# mcu.net
KiCad netlist of a schematic drawn in Altium Designer
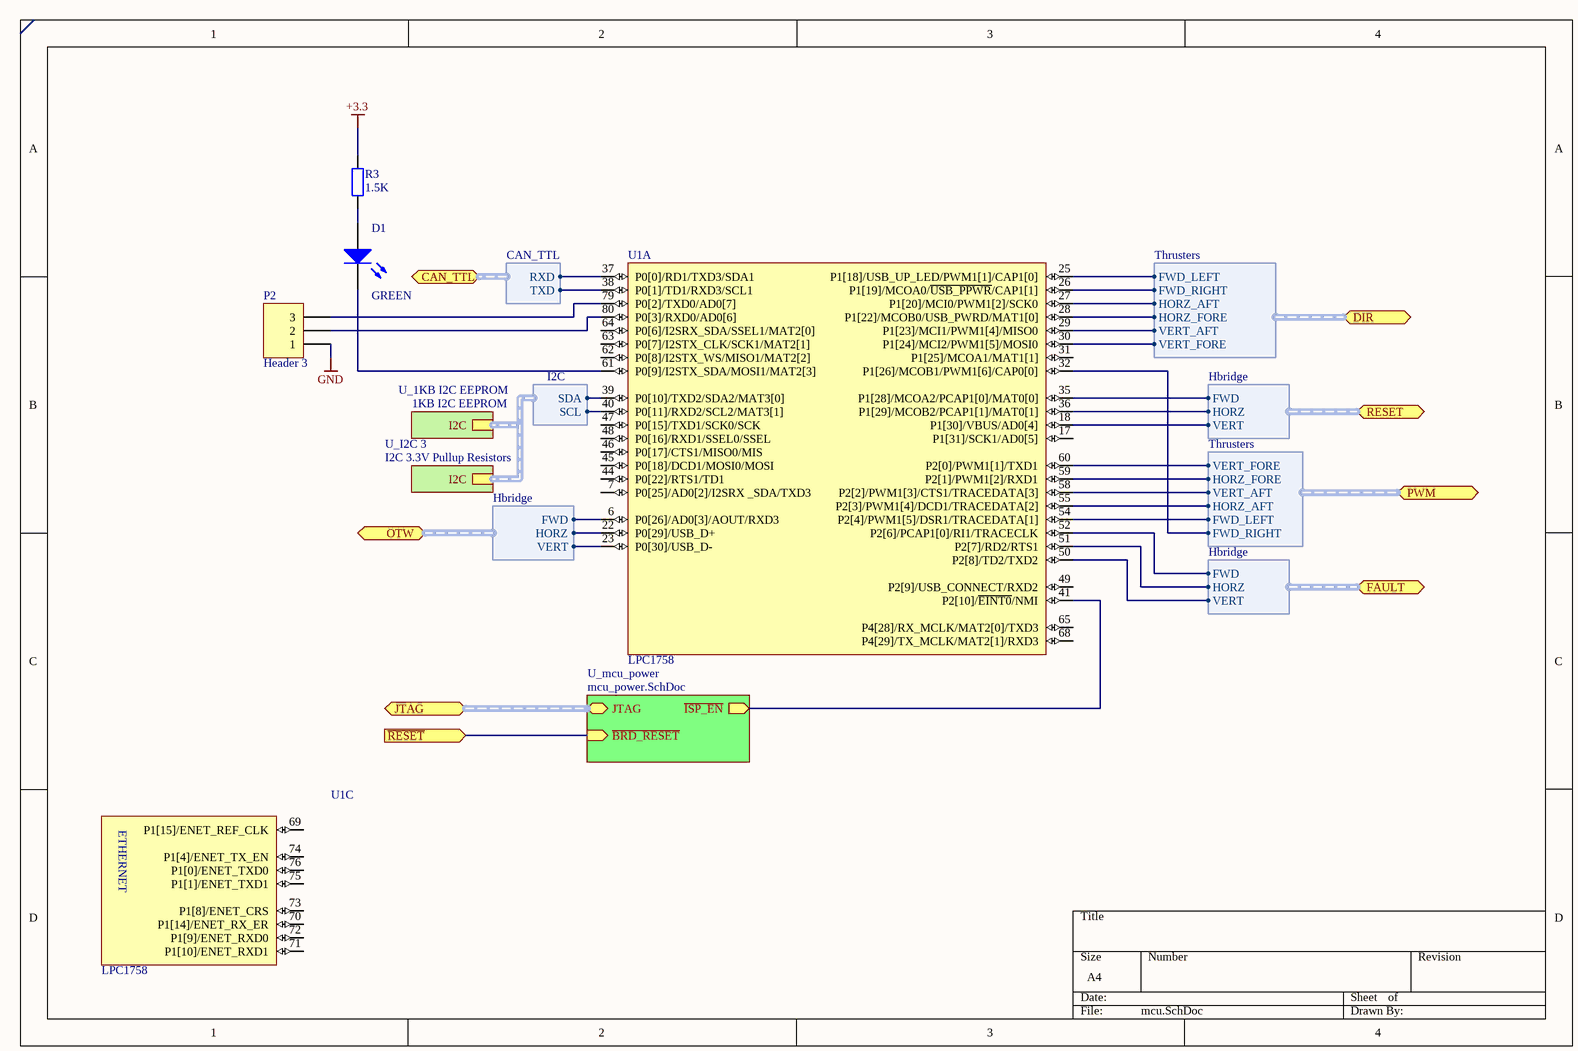
[diagram p0: mcu.SchDoc]

(export (version "E")
  (design (tool "Eeschema 10.0.6"))
  (components
    (comp (ref "D1")
      (value "GREEN")
      (footprint "LGQ971")
      (description "Typical RED, GREEN, YELLOW, AMBER GaAs LED")
      (libsource (lib "Miscellaneous Devices") (part "LED2"))
    )
    (comp (ref "P2")
      (value "Header 3")
      (footprint "HDR1X3")
      (description "Header, 3-Pin")
      (fields (field (name "PUBLISHER") "Altium Limited"))
      (libsource (lib "Miscellaneous Connectors") (part "Header 3"))
    )
    (comp (ref "R3")
      (value "1.5K")
      (footprint "R0603")
      (description "Resistor")
      (fields (field (name "Comment") "Res"))
      (libsource (lib "Miscellaneous Devices") (part "Res2"))
    )
    (comp (ref "U1")
      (value "LPC1758")
      (footprint "LPC1758FBD80")
      (description "NXP - LPC1758FBD80 - MCU, 32BIT, ARM CORTEX M3, 80LQFP")
      (libsource (lib "LPC1758") (part "LPC1758"))
    )
  )
  (nets
    (net (code "6") (name "+3.3") (class "Default")
      (node (ref "R3") (pin "2") (pinfunction "2_2") (pintype "passive"))
    )
    (net (code "8") (name "/RXD") (class "Default")
      (node (ref "U1") (pin "37") (pinfunction "P0[0]/RD1/TXD3/SDA1_37") (pintype "bidirectional"))
    )
    (net (code "9") (name "/SCL") (class "Default")
      (node (ref "U1") (pin "40") (pinfunction "P0[11]/RXD2/SCL2/MAT3[1]_40") (pintype "bidirectional"))
    )
    (net (code "10") (name "/SDA") (class "Default")
      (node (ref "U1") (pin "39") (pinfunction "P0[10]/TXD2/SDA2/MAT3[0]_39") (pintype "bidirectional"))
    )
    (net (code "11") (name "/TXD") (class "Default")
      (node (ref "U1") (pin "38") (pinfunction "P0[1]/TD1/RXD3/SCL1_38") (pintype "bidirectional"))
    )
    (net (code "16") (name "/~{ISP_EN}") (class "Default")
      (node (ref "U1") (pin "41") (pinfunction "P2[10]/~{EINT0}/NMI_41") (pintype "bidirectional"))
    )
    (net (code "18") (name "GND") (class "Default")
      (node (ref "P2") (pin "1") (pinfunction "1_1") (pintype "passive"))
    )
    (net (code "19") (name "Net-(D1-A)") (class "Default")
      (node (ref "D1") (pin "1") (pinfunction "A_1") (pintype "passive"))
      (node (ref "R3") (pin "1") (pinfunction "1_1") (pintype "passive"))
    )
    (net (code "20") (name "Net-(D1-K)") (class "Default")
      (node (ref "D1") (pin "2") (pinfunction "K_2") (pintype "passive"))
      (node (ref "U1") (pin "61") (pinfunction "P0[9]/I2STX_SDA/MOSI1/MAT2[3]_61") (pintype "bidirectional"))
    )
    (net (code "21") (name "Net-(U1A-P0[2]{slash}TXD0{slash}AD0[7])") (class "Default")
      (node (ref "P2") (pin "3") (pinfunction "3_3") (pintype "passive"))
      (node (ref "U1") (pin "79") (pinfunction "P0[2]/TXD0/AD0[7]_79") (pintype "bidirectional"))
    )
    (net (code "22") (name "Net-(U1A-P0[3]{slash}RXD0{slash}AD0[6])") (class "Default")
      (node (ref "P2") (pin "2") (pinfunction "2_2") (pintype "passive"))
      (node (ref "U1") (pin "80") (pinfunction "P0[3]/RXD0/AD0[6]_80") (pintype "bidirectional"))
    )
    (net (code "23") (name "unconnected-(U1A-P0[6]{slash}I2SRX_SDA{slash}SSEL1{slash}MAT2[0]-Pad64)") (class "Default")
      (node (ref "U1") (pin "64") (pinfunction "P0[6]/I2SRX_SDA/SSEL1/MAT2[0]_64") (pintype "bidirectional"))
    )
    (net (code "24") (name "unconnected-(U1A-P0[7]{slash}I2STX_CLK{slash}SCK1{slash}MAT2[1]-Pad63)") (class "Default")
      (node (ref "U1") (pin "63") (pinfunction "P0[7]/I2STX_CLK/SCK1/MAT2[1]_63") (pintype "bidirectional"))
    )
    (net (code "25") (name "unconnected-(U1A-P0[8]{slash}I2STX_WS{slash}MISO1{slash}MAT2[2]-Pad62)") (class "Default")
      (node (ref "U1") (pin "62") (pinfunction "P0[8]/I2STX_WS/MISO1/MAT2[2]_62") (pintype "bidirectional"))
    )
    (net (code "26") (name "unconnected-(U1A-P0[15]{slash}TXD1{slash}SCK0{slash}SCK-Pad47)") (class "Default")
      (node (ref "U1") (pin "47") (pinfunction "P0[15]/TXD1/SCK0/SCK_47") (pintype "bidirectional"))
    )
    (net (code "27") (name "unconnected-(U1A-P0[16]{slash}RXD1{slash}SSEL0{slash}SSEL-Pad48)") (class "Default")
      (node (ref "U1") (pin "48") (pinfunction "P0[16]/RXD1/SSEL0/SSEL_48") (pintype "bidirectional"))
    )
    (net (code "28") (name "unconnected-(U1A-P0[17]{slash}CTS1{slash}MISO0{slash}MIS-Pad46)") (class "Default")
      (node (ref "U1") (pin "46") (pinfunction "P0[17]/CTS1/MISO0/MIS_46") (pintype "bidirectional"))
    )
    (net (code "29") (name "unconnected-(U1A-P0[18]{slash}DCD1{slash}MOSI0{slash}MOSI-Pad45)") (class "Default")
      (node (ref "U1") (pin "45") (pinfunction "P0[18]/DCD1/MOSI0/MOSI_45") (pintype "bidirectional"))
    )
    (net (code "30") (name "unconnected-(U1A-P0[22]{slash}RTS1{slash}TD1-Pad44)") (class "Default")
      (node (ref "U1") (pin "44") (pinfunction "P0[22]/RTS1/TD1_44") (pintype "bidirectional"))
    )
    (net (code "31") (name "unconnected-(U1A-P0[25]{slash}AD0[2]{slash}I2SRX__SDA{slash}TXD3-Pad7)") (class "Default")
      (node (ref "U1") (pin "7") (pinfunction "P0[25]/AD0[2]/I2SRX__SDA/TXD3_7") (pintype "bidirectional"))
    )
    (net (code "32") (name "unconnected-(U1A-P0[26]{slash}AD0[3]{slash}AOUT{slash}RXD3-Pad6)") (class "Default")
      (node (ref "U1") (pin "6") (pinfunction "P0[26]/AD0[3]/AOUT/RXD3_6") (pintype "bidirectional"))
    )
    (net (code "33") (name "unconnected-(U1A-P0[29]{slash}USB_D+-Pad22)") (class "Default")
      (node (ref "U1") (pin "22") (pinfunction "P0[29]/USB_D+_22") (pintype "bidirectional"))
    )
    (net (code "34") (name "unconnected-(U1A-P0[30]{slash}USB_D--Pad23)") (class "Default")
      (node (ref "U1") (pin "23") (pinfunction "P0[30]/USB_D-_23") (pintype "bidirectional"))
    )
    (net (code "35") (name "unconnected-(U1A-P1[18]{slash}USB_UP_LED{slash}PWM1[1]{slash}CAP1[0]-Pad25)") (class "Default")
      (node (ref "U1") (pin "25") (pinfunction "P1[18]/USB_UP_LED/PWM1[1]/CAP1[0]_25") (pintype "bidirectional"))
    )
    (net (code "36") (name "unconnected-(U1A-P1[19]{slash}MCOA0{slash}~{USB_PPWR}{slash}CAP1[1]-Pad26)") (class "Default")
      (node (ref "U1") (pin "26") (pinfunction "P1[19]/MCOA0/~{USB_PPWR}/CAP1[1]_26") (pintype "bidirectional"))
    )
    (net (code "37") (name "unconnected-(U1A-P1[20]{slash}MCI0{slash}PWM1[2]{slash}SCK0-Pad27)") (class "Default")
      (node (ref "U1") (pin "27") (pinfunction "P1[20]/MCI0/PWM1[2]/SCK0_27") (pintype "bidirectional"))
    )
    (net (code "38") (name "unconnected-(U1A-P1[22]{slash}MCOB0{slash}USB_PWRD{slash}MAT1[0]-Pad28)") (class "Default")
      (node (ref "U1") (pin "28") (pinfunction "P1[22]/MCOB0/USB_PWRD/MAT1[0]_28") (pintype "bidirectional"))
    )
    (net (code "39") (name "unconnected-(U1A-P1[23]{slash}MCI1{slash}PWM1[4]{slash}MISO0-Pad29)") (class "Default")
      (node (ref "U1") (pin "29") (pinfunction "P1[23]/MCI1/PWM1[4]/MISO0_29") (pintype "bidirectional"))
    )
    (net (code "40") (name "unconnected-(U1A-P1[24]{slash}MCI2{slash}PWM1[5]{slash}MOSI0-Pad30)") (class "Default")
      (node (ref "U1") (pin "30") (pinfunction "P1[24]/MCI2/PWM1[5]/MOSI0_30") (pintype "bidirectional"))
    )
    (net (code "41") (name "unconnected-(U1A-P1[25]{slash}MCOA1{slash}MAT1[1]-Pad31)") (class "Default")
      (node (ref "U1") (pin "31") (pinfunction "P1[25]/MCOA1/MAT1[1]_31") (pintype "bidirectional"))
    )
    (net (code "42") (name "unconnected-(U1A-P1[26]{slash}MCOB1{slash}PWM1[6]{slash}CAP0[0]-Pad32)") (class "Default")
      (node (ref "U1") (pin "32") (pinfunction "P1[26]/MCOB1/PWM1[6]/CAP0[0]_32") (pintype "bidirectional"))
    )
    (net (code "43") (name "unconnected-(U1A-P1[28]{slash}MCOA2{slash}PCAP1[0]{slash}MAT0[0]-Pad35)") (class "Default")
      (node (ref "U1") (pin "35") (pinfunction "P1[28]/MCOA2/PCAP1[0]/MAT0[0]_35") (pintype "bidirectional"))
    )
    (net (code "44") (name "unconnected-(U1A-P1[29]{slash}MCOB2{slash}PCAP1[1]{slash}MAT0[1]-Pad36)") (class "Default")
      (node (ref "U1") (pin "36") (pinfunction "P1[29]/MCOB2/PCAP1[1]/MAT0[1]_36") (pintype "bidirectional"))
    )
    (net (code "45") (name "unconnected-(U1A-P1[30]{slash}VBUS{slash}AD0[4]-Pad18)") (class "Default")
      (node (ref "U1") (pin "18") (pinfunction "P1[30]/VBUS/AD0[4]_18") (pintype "bidirectional"))
    )
    (net (code "46") (name "unconnected-(U1A-P1[31]{slash}SCK1{slash}AD0[5]-Pad17)") (class "Default")
      (node (ref "U1") (pin "17") (pinfunction "P1[31]/SCK1/AD0[5]_17") (pintype "bidirectional"))
    )
    (net (code "47") (name "unconnected-(U1A-P2[0]{slash}PWM1[1]{slash}TXD1-Pad60)") (class "Default")
      (node (ref "U1") (pin "60") (pinfunction "P2[0]/PWM1[1]/TXD1_60") (pintype "bidirectional"))
    )
    (net (code "48") (name "unconnected-(U1A-P2[1]{slash}PWM1[2]{slash}RXD1-Pad59)") (class "Default")
      (node (ref "U1") (pin "59") (pinfunction "P2[1]/PWM1[2]/RXD1_59") (pintype "bidirectional"))
    )
    (net (code "49") (name "unconnected-(U1A-P2[2]{slash}PWM1[3]{slash}CTS1{slash}TRACEDATA[3]-Pad58)") (class "Default")
      (node (ref "U1") (pin "58") (pinfunction "P2[2]/PWM1[3]/CTS1/TRACEDATA[3]_58") (pintype "bidirectional"))
    )
    (net (code "50") (name "unconnected-(U1A-P2[3]{slash}PWM1[4]{slash}DCD1{slash}TRACEDATA[2]-Pad55)") (class "Default")
      (node (ref "U1") (pin "55") (pinfunction "P2[3]/PWM1[4]/DCD1/TRACEDATA[2]_55") (pintype "bidirectional"))
    )
    (net (code "51") (name "unconnected-(U1A-P2[4]{slash}PWM1[5]{slash}DSR1{slash}TRACEDATA[1]-Pad54)") (class "Default")
      (node (ref "U1") (pin "54") (pinfunction "P2[4]/PWM1[5]/DSR1/TRACEDATA[1]_54") (pintype "bidirectional"))
    )
    (net (code "52") (name "unconnected-(U1A-P2[6]{slash}PCAP1[0]{slash}RI1{slash}TRACECLK-Pad52)") (class "Default")
      (node (ref "U1") (pin "52") (pinfunction "P2[6]/PCAP1[0]/RI1/TRACECLK_52") (pintype "bidirectional"))
    )
    (net (code "53") (name "unconnected-(U1A-P2[7]{slash}RD2{slash}RTS1-Pad51)") (class "Default")
      (node (ref "U1") (pin "51") (pinfunction "P2[7]/RD2/RTS1_51") (pintype "bidirectional"))
    )
    (net (code "54") (name "unconnected-(U1A-P2[8]{slash}TD2{slash}TXD2-Pad50)") (class "Default")
      (node (ref "U1") (pin "50") (pinfunction "P2[8]/TD2/TXD2_50") (pintype "bidirectional"))
    )
    (net (code "55") (name "unconnected-(U1A-P2[9]{slash}USB_CONNECT{slash}RXD2-Pad49)") (class "Default")
      (node (ref "U1") (pin "49") (pinfunction "P2[9]/USB_CONNECT/RXD2_49") (pintype "bidirectional"))
    )
    (net (code "56") (name "unconnected-(U1A-P4[28]{slash}RX_MCLK{slash}MAT2[0]{slash}TXD3-Pad65)") (class "Default")
      (node (ref "U1") (pin "65") (pinfunction "P4[28]/RX_MCLK/MAT2[0]/TXD3_65") (pintype "bidirectional"))
    )
    (net (code "57") (name "unconnected-(U1A-P4[29]{slash}TX_MCLK{slash}MAT2[1]{slash}RXD3-Pad68)") (class "Default")
      (node (ref "U1") (pin "68") (pinfunction "P4[29]/TX_MCLK/MAT2[1]/RXD3_68") (pintype "bidirectional"))
    )
    (net (code "58") (name "unconnected-(U1C-P1[0]{slash}ENET_TXD0-Pad76)") (class "Default")
      (node (ref "U1") (pin "76") (pinfunction "P1[0]/ENET_TXD0_76") (pintype "bidirectional"))
    )
    (net (code "59") (name "unconnected-(U1C-P1[1]{slash}ENET_TXD1-Pad75)") (class "Default")
      (node (ref "U1") (pin "75") (pinfunction "P1[1]/ENET_TXD1_75") (pintype "bidirectional"))
    )
    (net (code "60") (name "unconnected-(U1C-P1[4]{slash}ENET_TX_EN-Pad74)") (class "Default")
      (node (ref "U1") (pin "74") (pinfunction "P1[4]/ENET_TX_EN_74") (pintype "bidirectional"))
    )
    (net (code "61") (name "unconnected-(U1C-P1[8]{slash}ENET_CRS-Pad73)") (class "Default")
      (node (ref "U1") (pin "73") (pinfunction "P1[8]/ENET_CRS_73") (pintype "bidirectional"))
    )
    (net (code "62") (name "unconnected-(U1C-P1[9]{slash}ENET_RXD0-Pad72)") (class "Default")
      (node (ref "U1") (pin "72") (pinfunction "P1[9]/ENET_RXD0_72") (pintype "bidirectional"))
    )
    (net (code "63") (name "unconnected-(U1C-P1[10]{slash}ENET_RXD1-Pad71)") (class "Default")
      (node (ref "U1") (pin "71") (pinfunction "P1[10]/ENET_RXD1_71") (pintype "bidirectional"))
    )
    (net (code "64") (name "unconnected-(U1C-P1[14]{slash}ENET_RX_ER-Pad70)") (class "Default")
      (node (ref "U1") (pin "70") (pinfunction "P1[14]/ENET_RX_ER_70") (pintype "bidirectional"))
    )
    (net (code "65") (name "unconnected-(U1C-P1[15]{slash}ENET_REF_CLK-Pad69)") (class "Default")
      (node (ref "U1") (pin "69") (pinfunction "P1[15]/ENET_REF_CLK_69") (pintype "bidirectional"))
    )
  )
)
